# arduino_seringa.net
KiCad netlist of a schematic drawn in EAGLE
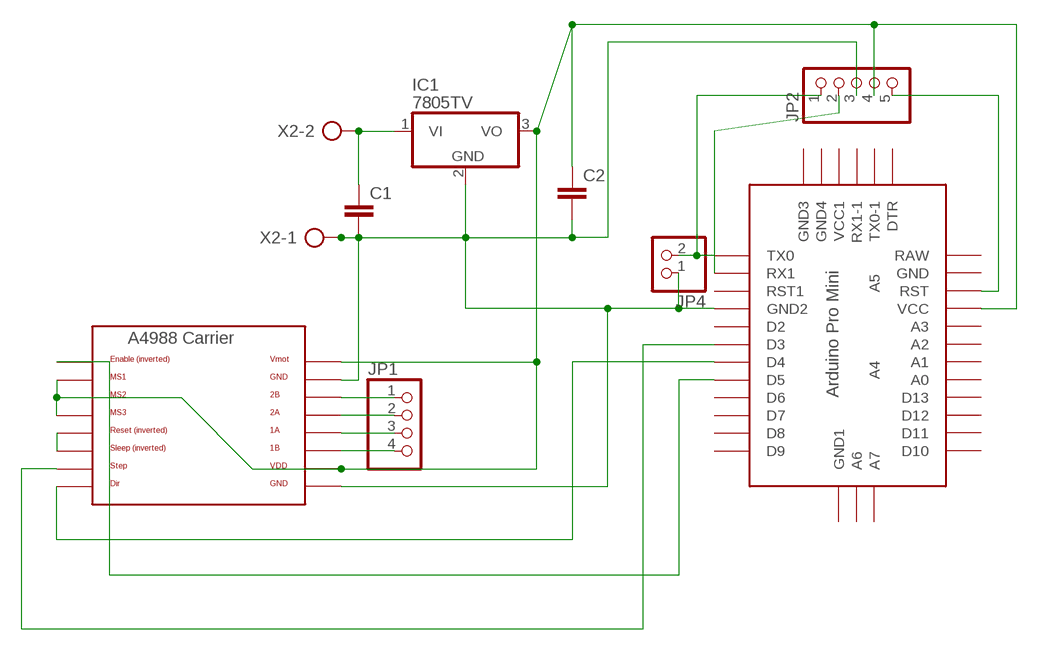
[diagram p0: schematic, sheet 1]

(export (version "E")
  (design (tool "Eeschema 10.0.6"))
  (components
    (comp (ref "C1")
      (value "C5/3")
      (footprint "eagle-import:C5B3")
      (libsource (lib "eagle-import") (part "C5/3"))
    )
    (comp (ref "C2")
      (value "C5/3")
      (footprint "eagle-import:C5B3")
      (libsource (lib "eagle-import") (part "C5/3"))
    )
    (comp (ref "IC1")
      (value "7805TV")
      (footprint "eagle-import:TO220V")
      (libsource (lib "eagle-import") (part "78TV05"))
    )
    (comp (ref "JP1")
      (value "PINHD-1X4")
      (footprint "eagle-import:1X04")
      (libsource (lib "eagle-import") (part "PINHD-1X4"))
    )
    (comp (ref "JP2")
      (value "PINHD-1X5")
      (footprint "eagle-import:1X05")
      (libsource (lib "eagle-import") (part "PINHD-1X5"))
    )
    (comp (ref "JP4")
      (value "PINHD-1X2")
      (footprint "eagle-import:1X02")
      (libsource (lib "eagle-import") (part "PINHD-1X2"))
    )
    (comp (ref "U$1")
      (value "ABK-PRO-MINI")
      (footprint "eagle-import:ABK-PRO-MINI")
      (libsource (lib "eagle-import") (part "ABK-PRO-MINI"))
    )
    (comp (ref "U$2")
      (value "A4988BREAKOUT")
      (footprint "eagle-import:A4988BREAKOUT")
      (libsource (lib "eagle-import") (part "A4988BREAKOUT"))
    )
    (comp (ref "X2")
      (value "AK500/2")
      (footprint "eagle-import:AK500_2")
      (libsource (lib "eagle-import") (part "AK500/2"))
    )
  )
  (nets
    (net (code "1") (name "Net-(IC1-GND)") (class "Default")
      (node (ref "C1") (pin "2") (pinfunction "2_2") (pintype "passive"))
      (node (ref "C2") (pin "2") (pinfunction "2_2") (pintype "passive"))
      (node (ref "IC1") (pin "2") (pinfunction "GND_2") (pintype "passive"))
      (node (ref "JP2") (pin "3") (pinfunction "3_3") (pintype "passive"))
      (node (ref "JP4") (pin "1") (pinfunction "1_1") (pintype "passive"))
      (node (ref "U$1") (pin "GND1") (pinfunction "GND2_GND1") (pintype "bidirectional"))
      (node (ref "U$2") (pin "GND") (pinfunction "GND_GND") (pintype "power_in"))
      (node (ref "U$2") (pin "GND@0") (pinfunction "GND_GND@0") (pintype "power_in"))
      (node (ref "X2") (pin "1") (pinfunction "KL_1") (pintype "passive"))
    )
    (net (code "2") (name "Net-(IC1-VI)") (class "Default")
      (node (ref "C1") (pin "1") (pinfunction "1_1") (pintype "passive"))
      (node (ref "IC1") (pin "1") (pinfunction "VI_1") (pintype "input"))
      (node (ref "X2") (pin "2") (pinfunction "KL_2") (pintype "passive"))
    )
    (net (code "3") (name "Net-(IC1-VO)") (class "Default")
      (node (ref "C2") (pin "1") (pinfunction "1_1") (pintype "passive"))
      (node (ref "IC1") (pin "3") (pinfunction "VO_3") (pintype "passive"))
      (node (ref "JP2") (pin "4") (pinfunction "4_4") (pintype "passive"))
      (node (ref "U$1") (pin "VCC") (pinfunction "VCC_VCC") (pintype "bidirectional"))
      (node (ref "U$2") (pin "MS1") (pinfunction "MS1_MS1") (pintype "input"))
      (node (ref "U$2") (pin "MS2") (pinfunction "MS2_MS2") (pintype "input"))
      (node (ref "U$2") (pin "MS3") (pinfunction "MS3_MS3") (pintype "input"))
      (node (ref "U$2") (pin "VDD") (pinfunction "VDD_VDD") (pintype "power_in"))
      (node (ref "U$2") (pin "VMOT") (pinfunction "VMOT_VMOT") (pintype "power_in"))
    )
    (net (code "4") (name "Net-(JP1-Pad1)") (class "Default")
      (node (ref "JP1") (pin "1") (pinfunction "1_1") (pintype "passive"))
      (node (ref "U$2") (pin "2B") (pinfunction "2B_2B") (pintype "output"))
    )
    (net (code "5") (name "Net-(JP1-Pad2)") (class "Default")
      (node (ref "JP1") (pin "2") (pinfunction "2_2") (pintype "passive"))
      (node (ref "U$2") (pin "2A") (pinfunction "2A_2A") (pintype "output"))
    )
    (net (code "6") (name "Net-(JP1-Pad3)") (class "Default")
      (node (ref "JP1") (pin "3") (pinfunction "3_3") (pintype "passive"))
      (node (ref "U$2") (pin "1A") (pinfunction "1A_1A") (pintype "output"))
    )
    (net (code "7") (name "Net-(JP1-Pad4)") (class "Default")
      (node (ref "JP1") (pin "4") (pinfunction "4_4") (pintype "passive"))
      (node (ref "U$2") (pin "1B") (pinfunction "1B_1B") (pintype "output"))
    )
    (net (code "8") (name "Net-(JP2-Pad1)") (class "Default")
      (node (ref "JP2") (pin "1") (pinfunction "1_1") (pintype "passive"))
      (node (ref "JP4") (pin "2") (pinfunction "2_2") (pintype "passive"))
      (node (ref "U$1") (pin "TX0") (pinfunction "TX0_TX0") (pintype "bidirectional"))
    )
    (net (code "9") (name "Net-(JP2-Pad2)") (class "Default")
      (node (ref "JP2") (pin "2") (pinfunction "2_2") (pintype "passive"))
      (node (ref "U$1") (pin "RX1") (pinfunction "RX1_RX1") (pintype "bidirectional"))
    )
    (net (code "10") (name "Net-(JP2-Pad5)") (class "Default")
      (node (ref "JP2") (pin "5") (pinfunction "5_5") (pintype "passive"))
      (node (ref "U$1") (pin "RST") (pinfunction "RST_RST") (pintype "bidirectional"))
    )
    (net (code "11") (name "Net-(U$1-PadD3)") (class "Default")
      (node (ref "U$1") (pin "D3") (pinfunction "D3_D3") (pintype "bidirectional"))
      (node (ref "U$2") (pin "STEP") (pinfunction "STEP_STEP") (pintype "input"))
    )
    (net (code "12") (name "Net-(U$1-PadD4)") (class "Default")
      (node (ref "U$1") (pin "D4") (pinfunction "D4_D4") (pintype "bidirectional"))
      (node (ref "U$2") (pin "DIR") (pinfunction "DIR_DIR") (pintype "input"))
    )
    (net (code "13") (name "Net-(U$1-PadD5)") (class "Default")
      (node (ref "U$1") (pin "D5") (pinfunction "D5_D5") (pintype "bidirectional"))
      (node (ref "U$2") (pin "EN") (pinfunction "EN_EN") (pintype "input"))
    )
    (net (code "14") (name "Net-(U$2-SLEEP)") (class "Default")
      (node (ref "U$2") (pin "RST") (pinfunction "RST_RST") (pintype "input"))
      (node (ref "U$2") (pin "SLP") (pinfunction "SLEEP_SLP") (pintype "input"))
    )
    (net (code "15") (name "unconnected-(U$1-GND1-PadGND4)") (class "Default")
      (node (ref "U$1") (pin "GND4") (pinfunction "GND1_GND4") (pintype "bidirectional"))
    )
    (net (code "16") (name "unconnected-(U$1-GND3-PadGND2)") (class "Default")
      (node (ref "U$1") (pin "GND2") (pinfunction "GND3_GND2") (pintype "bidirectional"))
    )
    (net (code "17") (name "unconnected-(U$1-GND4-PadGND3)") (class "Default")
      (node (ref "U$1") (pin "GND3") (pinfunction "GND4_GND3") (pintype "bidirectional"))
    )
    (net (code "18") (name "unconnected-(U$1-PadA0)") (class "Default")
      (node (ref "U$1") (pin "A0") (pinfunction "A0_A0") (pintype "bidirectional"))
    )
    (net (code "19") (name "unconnected-(U$1-PadA1)") (class "Default")
      (node (ref "U$1") (pin "A1") (pinfunction "A1_A1") (pintype "bidirectional"))
    )
    (net (code "20") (name "unconnected-(U$1-PadA2)") (class "Default")
      (node (ref "U$1") (pin "A2") (pinfunction "A2_A2") (pintype "bidirectional"))
    )
    (net (code "21") (name "unconnected-(U$1-PadA3)") (class "Default")
      (node (ref "U$1") (pin "A3") (pinfunction "A3_A3") (pintype "bidirectional"))
    )
    (net (code "22") (name "unconnected-(U$1-PadA4)") (class "Default")
      (node (ref "U$1") (pin "A4") (pinfunction "A4_A4") (pintype "bidirectional"))
    )
    (net (code "23") (name "unconnected-(U$1-PadA5)") (class "Default")
      (node (ref "U$1") (pin "A5") (pinfunction "A5_A5") (pintype "bidirectional"))
    )
    (net (code "24") (name "unconnected-(U$1-PadA6)") (class "Default")
      (node (ref "U$1") (pin "A6") (pinfunction "A6_A6") (pintype "bidirectional"))
    )
    (net (code "25") (name "unconnected-(U$1-PadA7)") (class "Default")
      (node (ref "U$1") (pin "A7") (pinfunction "A7_A7") (pintype "bidirectional"))
    )
    (net (code "26") (name "unconnected-(U$1-PadD2)") (class "Default")
      (node (ref "U$1") (pin "D2") (pinfunction "D2_D2") (pintype "bidirectional"))
    )
    (net (code "27") (name "unconnected-(U$1-PadD6)") (class "Default")
      (node (ref "U$1") (pin "D6") (pinfunction "D6_D6") (pintype "bidirectional"))
    )
    (net (code "28") (name "unconnected-(U$1-PadD7)") (class "Default")
      (node (ref "U$1") (pin "D7") (pinfunction "D7_D7") (pintype "bidirectional"))
    )
    (net (code "29") (name "unconnected-(U$1-PadD8)") (class "Default")
      (node (ref "U$1") (pin "D8") (pinfunction "D8_D8") (pintype "bidirectional"))
    )
    (net (code "30") (name "unconnected-(U$1-PadD9)") (class "Default")
      (node (ref "U$1") (pin "D9") (pinfunction "D9_D9") (pintype "bidirectional"))
    )
    (net (code "31") (name "unconnected-(U$1-PadD10)") (class "Default")
      (node (ref "U$1") (pin "D10") (pinfunction "D10_D10") (pintype "bidirectional"))
    )
    (net (code "32") (name "unconnected-(U$1-PadD11)") (class "Default")
      (node (ref "U$1") (pin "D11") (pinfunction "D11_D11") (pintype "bidirectional"))
    )
    (net (code "33") (name "unconnected-(U$1-PadD12)") (class "Default")
      (node (ref "U$1") (pin "D12") (pinfunction "D12_D12") (pintype "bidirectional"))
    )
    (net (code "34") (name "unconnected-(U$1-PadD13)") (class "Default")
      (node (ref "U$1") (pin "D13") (pinfunction "D13_D13") (pintype "bidirectional"))
    )
    (net (code "35") (name "unconnected-(U$1-PadDTR)") (class "Default")
      (node (ref "U$1") (pin "DTR") (pinfunction "DTR_DTR") (pintype "bidirectional"))
    )
    (net (code "36") (name "unconnected-(U$1-PadGND)") (class "Default")
      (node (ref "U$1") (pin "GND") (pinfunction "GND_GND") (pintype "bidirectional"))
    )
    (net (code "37") (name "unconnected-(U$1-PadRAW)") (class "Default")
      (node (ref "U$1") (pin "RAW") (pinfunction "RAW_RAW") (pintype "bidirectional"))
    )
    (net (code "38") (name "unconnected-(U$1-PadRST1)") (class "Default")
      (node (ref "U$1") (pin "RST1") (pinfunction "RST1_RST1") (pintype "bidirectional"))
    )
    (net (code "39") (name "unconnected-(U$1-PadRX1-1)") (class "Default")
      (node (ref "U$1") (pin "RX1-1") (pinfunction "RX1-1_RX1-1") (pintype "bidirectional"))
    )
    (net (code "40") (name "unconnected-(U$1-PadTX0-1)") (class "Default")
      (node (ref "U$1") (pin "TX0-1") (pinfunction "TX0-1_TX0-1") (pintype "bidirectional"))
    )
    (net (code "41") (name "unconnected-(U$1-PadVCC1)") (class "Default")
      (node (ref "U$1") (pin "VCC1") (pinfunction "VCC1_VCC1") (pintype "bidirectional"))
    )
  )
)
